# breadboarddev.net
KiCad netlist of a schematic drawn in EAGLE
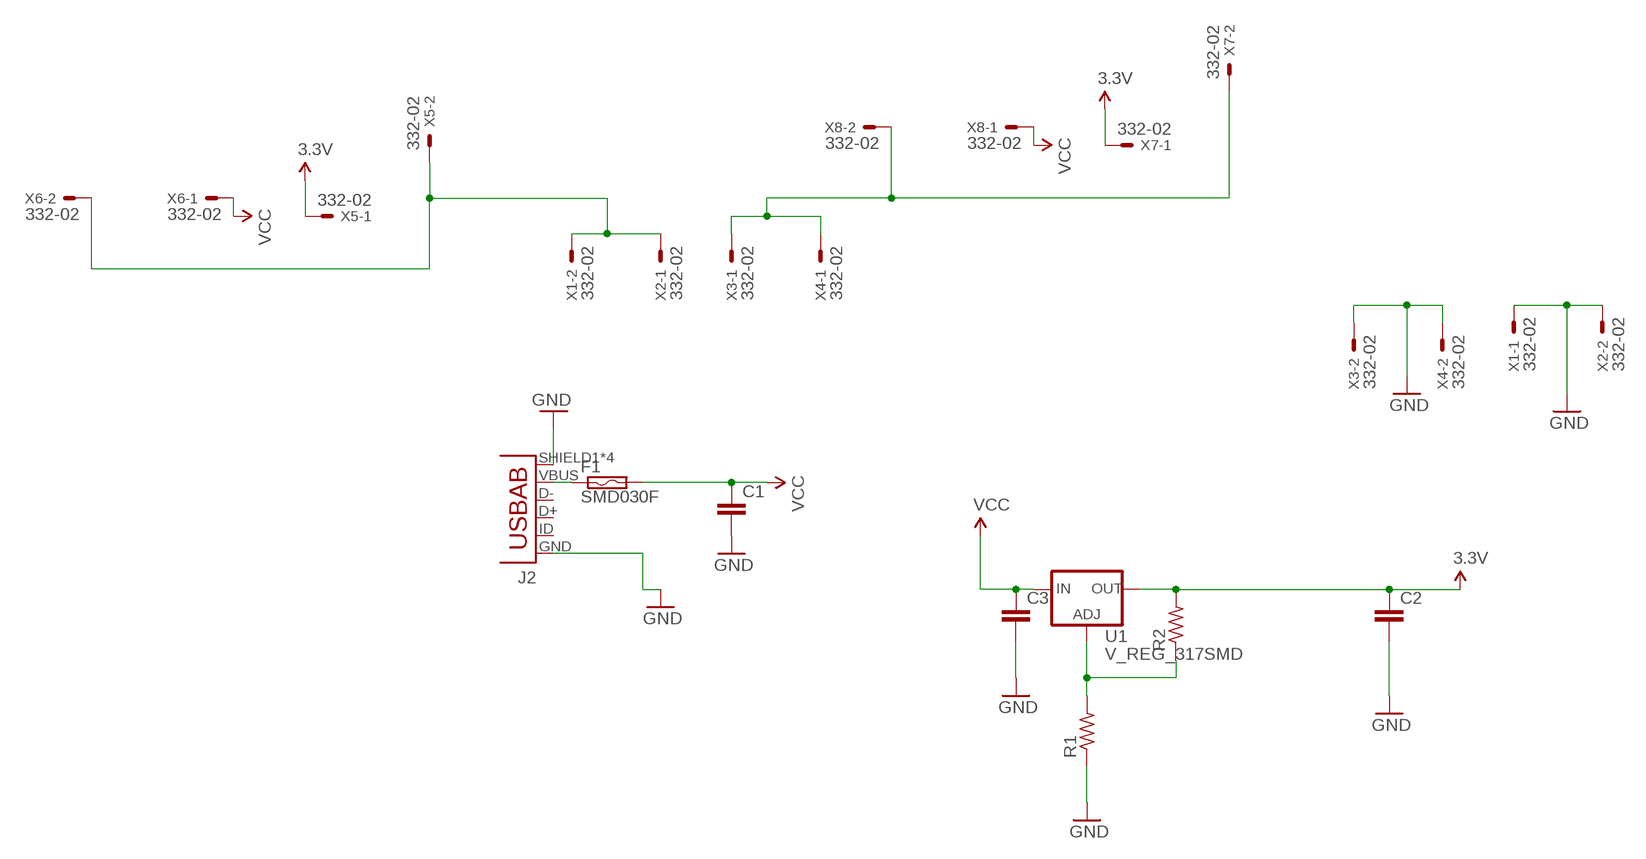
[diagram p0: schematic, sheet 1]

(export (version "E")
  (design (tool "Eeschema 10.0.6"))
  (components
    (comp (ref "C1")
      (value "C-EUC0603K")
      (footprint "eagle-import:C0603K")
      (libsource (lib "eagle-import") (part "C-EUC0603K"))
    )
    (comp (ref "C2")
      (value "C-EUC0603K")
      (footprint "eagle-import:C0603K")
      (libsource (lib "eagle-import") (part "C-EUC0603K"))
    )
    (comp (ref "C3")
      (value "C-EUC0603K")
      (footprint "eagle-import:C0603K")
      (libsource (lib "eagle-import") (part "C-EUC0603K"))
    )
    (comp (ref "F1")
      (value "SMD030F")
      (footprint "eagle-import:SMD050F")
      (libsource (lib "eagle-import") (part "SMDF030"))
    )
    (comp (ref "J2")
      (value "USB-AB")
      (footprint "eagle-import:USB-AB-MICRO-SMD")
      (libsource (lib "eagle-import") (part "USB-AB"))
    )
    (comp (ref "R1")
      (value "R-US_MELF0204W")
      (footprint "eagle-import:MINI_MELF-0204W")
      (libsource (lib "eagle-import") (part "R-US_MELF0204W"))
    )
    (comp (ref "R2")
      (value "R-US_MELF0204W")
      (footprint "eagle-import:MINI_MELF-0204W")
      (libsource (lib "eagle-import") (part "R-US_MELF0204W"))
    )
    (comp (ref "U1")
      (value "V_REG_317SMD")
      (footprint "eagle-import:SOT223")
      (libsource (lib "eagle-import") (part "V_REG_317SMD"))
    )
    (comp (ref "X1")
      (value "332-02")
      (footprint "eagle-import:332-02")
      (libsource (lib "eagle-import") (part "332-02"))
    )
    (comp (ref "X2")
      (value "332-02")
      (footprint "eagle-import:332-02")
      (libsource (lib "eagle-import") (part "332-02"))
    )
    (comp (ref "X3")
      (value "332-02")
      (footprint "eagle-import:332-02")
      (libsource (lib "eagle-import") (part "332-02"))
    )
    (comp (ref "X4")
      (value "332-02")
      (footprint "eagle-import:332-02")
      (libsource (lib "eagle-import") (part "332-02"))
    )
    (comp (ref "X5")
      (value "332-02")
      (footprint "eagle-import:332-02")
      (libsource (lib "eagle-import") (part "332-02"))
    )
    (comp (ref "X6")
      (value "332-02")
      (footprint "eagle-import:332-02")
      (libsource (lib "eagle-import") (part "332-02"))
    )
    (comp (ref "X7")
      (value "332-02")
      (footprint "eagle-import:332-02")
      (libsource (lib "eagle-import") (part "332-02"))
    )
    (comp (ref "X8")
      (value "332-02")
      (footprint "eagle-import:332-02")
      (libsource (lib "eagle-import") (part "332-02"))
    )
  )
  (nets
    (net (code "1") (name "3.3V") (class "Default")
      (node (ref "C2") (pin "1") (pinfunction "1_1") (pintype "passive"))
      (node (ref "R2") (pin "2") (pinfunction "2_2") (pintype "passive"))
      (node (ref "U1") (pin "2") (pinfunction "OUT_2") (pintype "output"))
      (node (ref "X5") (pin "1") (pinfunction "S_1") (pintype "passive"))
      (node (ref "X7") (pin "1") (pinfunction "S_1") (pintype "passive"))
    )
    (net (code "2") (name "GND") (class "Default")
      (node (ref "C1") (pin "2") (pinfunction "2_2") (pintype "passive"))
      (node (ref "C2") (pin "2") (pinfunction "2_2") (pintype "passive"))
      (node (ref "C3") (pin "2") (pinfunction "2_2") (pintype "passive"))
      (node (ref "J2") (pin "GND") (pinfunction "GND_GND") (pintype "bidirectional"))
      (node (ref "J2") (pin "SHIELD1") (pinfunction "SHIELD_SHIELD1") (pintype "bidirectional"))
      (node (ref "J2") (pin "SHIELD2") (pinfunction "SHIELD_SHIELD2") (pintype "bidirectional"))
      (node (ref "J2") (pin "SHIELD3") (pinfunction "SHIELD_SHIELD3") (pintype "bidirectional"))
      (node (ref "J2") (pin "SHIELD4") (pinfunction "SHIELD_SHIELD4") (pintype "bidirectional"))
      (node (ref "R1") (pin "1") (pinfunction "1_1") (pintype "passive"))
      (node (ref "X1") (pin "1") (pinfunction "S_1") (pintype "passive"))
      (node (ref "X2") (pin "2") (pinfunction "S_2") (pintype "passive"))
      (node (ref "X3") (pin "2") (pinfunction "S_2") (pintype "passive"))
      (node (ref "X4") (pin "2") (pinfunction "S_2") (pintype "passive"))
    )
    (net (code "3") (name "Net-(F1-Pad1)") (class "Default")
      (node (ref "F1") (pin "1") (pinfunction "1_1") (pintype "passive"))
      (node (ref "J2") (pin "VBUS") (pinfunction "VBUS_VBUS") (pintype "bidirectional"))
    )
    (net (code "4") (name "Net-(U1-ADJ)") (class "Default")
      (node (ref "R1") (pin "2") (pinfunction "2_2") (pintype "passive"))
      (node (ref "R2") (pin "1") (pinfunction "1_1") (pintype "passive"))
      (node (ref "U1") (pin "1") (pinfunction "ADJ_1") (pintype "input"))
    )
    (net (code "5") (name "Net-(X1B-S)") (class "Default")
      (node (ref "X1") (pin "2") (pinfunction "S_2") (pintype "passive"))
      (node (ref "X2") (pin "1") (pinfunction "S_1") (pintype "passive"))
      (node (ref "X5") (pin "2") (pinfunction "S_2") (pintype "passive"))
      (node (ref "X6") (pin "2") (pinfunction "S_2") (pintype "passive"))
    )
    (net (code "6") (name "Net-(X3A-S)") (class "Default")
      (node (ref "X3") (pin "1") (pinfunction "S_1") (pintype "passive"))
      (node (ref "X4") (pin "1") (pinfunction "S_1") (pintype "passive"))
      (node (ref "X7") (pin "2") (pinfunction "S_2") (pintype "passive"))
      (node (ref "X8") (pin "2") (pinfunction "S_2") (pintype "passive"))
    )
    (net (code "7") (name "VCC") (class "Default")
      (node (ref "C1") (pin "1") (pinfunction "1_1") (pintype "passive"))
      (node (ref "C3") (pin "1") (pinfunction "1_1") (pintype "passive"))
      (node (ref "F1") (pin "2") (pinfunction "2_2") (pintype "passive"))
      (node (ref "U1") (pin "3") (pinfunction "IN_3") (pintype "input"))
      (node (ref "X6") (pin "1") (pinfunction "S_1") (pintype "passive"))
      (node (ref "X8") (pin "1") (pinfunction "S_1") (pintype "passive"))
    )
    (net (code "8") (name "unconnected-(J2-PadD+)") (class "Default")
      (node (ref "J2") (pin "D+") (pinfunction "D+_D+") (pintype "bidirectional"))
    )
    (net (code "9") (name "unconnected-(J2-PadD-)") (class "Default")
      (node (ref "J2") (pin "D-") (pinfunction "D-_D-") (pintype "bidirectional"))
    )
    (net (code "10") (name "unconnected-(J2-USBID-PadID)") (class "Default")
      (node (ref "J2") (pin "ID") (pinfunction "USBID_ID") (pintype "bidirectional"))
    )
  )
)
